# com.net
KiCad netlist of a schematic drawn in Altium Designer
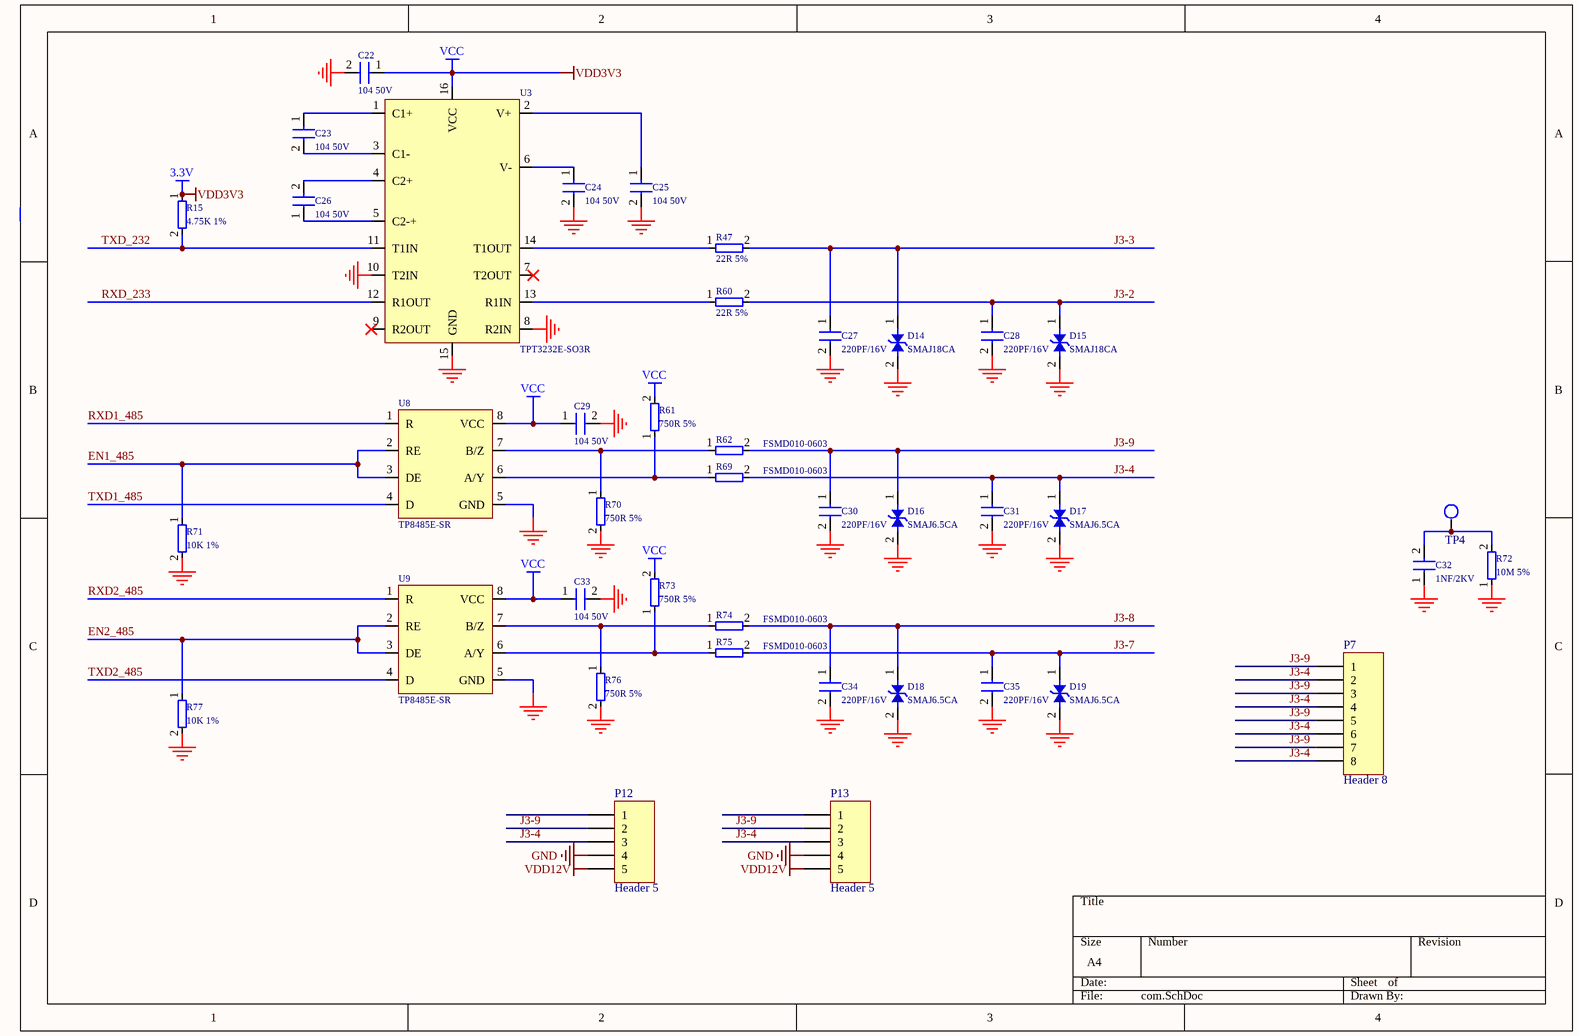
[diagram p0: com.SchDoc]

(export (version "E")
  (design (tool "Eeschema 10.0.6"))
  (components
    (comp (ref "C22") (value "104 50V") (footprint "0603C") (libsource (lib "*") (part "CAP")))
    (comp (ref "C23") (value "104 50V") (footprint "0603C") (libsource (lib "*") (part "CAP")))
    (comp (ref "C24") (value "104 50V") (footprint "0603C") (libsource (lib "*") (part "CAP")))
    (comp (ref "C25") (value "104 50V") (footprint "0603C") (libsource (lib "*") (part "CAP")))
    (comp (ref "C26") (value "104 50V") (footprint "0603C") (libsource (lib "*") (part "CAP")))
    (comp (ref "C27") (value "220PF/16V") (footprint "0603C") (libsource (lib "*") (part "CAP")))
    (comp (ref "C28") (value "220PF/16V") (footprint "0603C") (libsource (lib "*") (part "CAP")))
    (comp (ref "C29") (value "104 50V") (footprint "0603C") (libsource (lib "*") (part "CAP")))
    (comp (ref "C30") (value "220PF/16V") (footprint "0603C") (libsource (lib "*") (part "CAP")))
    (comp (ref "C31") (value "220PF/16V") (footprint "0603C") (libsource (lib "*") (part "CAP")))
    (comp (ref "C32") (value "1NF/2KV") (footprint "1206C") (libsource (lib "*") (part "CAP")))
    (comp (ref "C33") (value "104 50V") (footprint "0603C") (libsource (lib "*") (part "CAP")))
    (comp (ref "C34") (value "220PF/16V") (footprint "0603C") (libsource (lib "*") (part "CAP")))
    (comp (ref "C35") (value "220PF/16V") (footprint "0603C") (libsource (lib "*") (part "CAP")))
    (comp (ref "D14") (value "SMAJ18CA") (footprint "SMA") (libsource (lib "*") (part "D_ESD")))
    (comp (ref "D15") (value "SMAJ18CA") (footprint "SMA") (libsource (lib "*") (part "D_ESD")))
    (comp (ref "D16") (value "SMAJ6.5CA") (footprint "SMA") (libsource (lib "*") (part "D_ESD")))
    (comp (ref "D17") (value "SMAJ6.5CA") (footprint "SMA") (libsource (lib "*") (part "D_ESD")))
    (comp (ref "D18") (value "SMAJ6.5CA") (footprint "SMA") (libsource (lib "*") (part "D_ESD")))
    (comp (ref "D19") (value "SMAJ6.5CA") (footprint "SMA") (libsource (lib "*") (part "D_ESD")))
    (comp (ref "P7")
      (value "Header 8")
      (footprint "8X2.54MMZ")
      (description "Header, 8-Pin")
      (fields (field (name "PUBLISHER") "Altium Limited"))
      (libsource (lib "Miscellaneous Connectors") (part "Header 8"))
    )
    (comp (ref "P12")
      (value "Header 5")
      (footprint "5X2.54MMZ")
      (description "Header, 5-Pin")
      (fields (field (name "PUBLISHER") "Altium Limited"))
      (libsource (lib "Miscellaneous Connectors") (part "Header 5"))
    )
    (comp (ref "P13")
      (value "Header 5")
      (footprint "5X2.54MMZ")
      (description "Header, 5-Pin")
      (fields (field (name "PUBLISHER") "Altium Limited"))
      (libsource (lib "Miscellaneous Connectors") (part "Header 5"))
    )
    (comp (ref "R15") (value "4.75K 1%") (footprint "0603R") (libsource (lib "*") (part "RES")))
    (comp (ref "R47") (value "22R 5%") (footprint "0603R") (libsource (lib "*") (part "RES")))
    (comp (ref "R60") (value "22R 5%") (footprint "0603R") (libsource (lib "*") (part "RES")))
    (comp (ref "R61") (value "750R 5%") (footprint "0603R") (libsource (lib "*") (part "RES")))
    (comp (ref "R62") (value "FSMD010-0603") (footprint "0603R") (libsource (lib "*") (part "RES")))
    (comp (ref "R69") (value "FSMD010-0603") (footprint "0603R") (libsource (lib "*") (part "RES")))
    (comp (ref "R70") (value "750R 5%") (footprint "0603R") (libsource (lib "*") (part "RES")))
    (comp (ref "R71") (value "10K 1%") (footprint "0603R") (libsource (lib "*") (part "RES")))
    (comp (ref "R72") (value "10M 5%") (footprint "1206r") (libsource (lib "*") (part "RES")))
    (comp (ref "R73") (value "750R 5%") (footprint "0603R") (libsource (lib "*") (part "RES")))
    (comp (ref "R74") (value "FSMD010-0603") (footprint "0603R") (libsource (lib "*") (part "RES")))
    (comp (ref "R75") (value "FSMD010-0603") (footprint "0603R") (libsource (lib "*") (part "RES")))
    (comp (ref "R76") (value "750R 5%") (footprint "0603R") (libsource (lib "*") (part "RES")))
    (comp (ref "R77") (value "10K 1%") (footprint "0603R") (libsource (lib "*") (part "RES")))
    (comp (ref "TP4") (value "TPS") (footprint "tpd") (libsource (lib "stm32") (part "TPS")))
    (comp (ref "U3")
      (value "TPT3232E-SO3R")
      (footprint "SO-16Z")
      (libsource (lib "*") (part "TPT3232E-SO3R"))
    )
    (comp (ref "U8") (value "TP8485E-SR") (footprint "SO-8") (libsource (lib "*") (part "TP8485E-SR")))
    (comp (ref "U9") (value "TP8485E-SR") (footprint "SO-8") (libsource (lib "*") (part "TP8485E-SR")))
  )
  (nets
    (net (code "1") (name "/EN1_485") (class "Default")
      (node (ref "R71") (pin "1") (pinfunction "1_1") (pintype "passive"))
      (node (ref "U8") (pin "2") (pinfunction "RE_2") (pintype "passive"))
      (node (ref "U8") (pin "3") (pinfunction "DE_3") (pintype "passive"))
    )
    (net (code "2") (name "/EN2_485") (class "Default")
      (node (ref "R77") (pin "1") (pinfunction "1_1") (pintype "passive"))
      (node (ref "U9") (pin "2") (pinfunction "RE_2") (pintype "passive"))
      (node (ref "U9") (pin "3") (pinfunction "DE_3") (pintype "passive"))
    )
    (net (code "3") (name "/J3-2") (class "Default")
      (node (ref "C28") (pin "1") (pintype "passive"))
      (node (ref "D15") (pin "1") (pintype "passive"))
      (node (ref "R60") (pin "2") (pinfunction "2_2") (pintype "passive"))
    )
    (net (code "4") (name "/J3-3") (class "Default")
      (node (ref "C27") (pin "1") (pintype "passive"))
      (node (ref "D14") (pin "1") (pintype "passive"))
      (node (ref "R47") (pin "2") (pinfunction "2_2") (pintype "passive"))
    )
    (net (code "5") (name "/J3-4") (class "Default")
      (node (ref "C31") (pin "1") (pintype "passive"))
      (node (ref "D17") (pin "1") (pintype "passive"))
      (node (ref "P12") (pin "3") (pinfunction "3_3") (pintype "passive"))
      (node (ref "P13") (pin "3") (pinfunction "3_3") (pintype "passive"))
      (node (ref "P7") (pin "2") (pinfunction "2_2") (pintype "passive"))
      (node (ref "P7") (pin "4") (pinfunction "4_4") (pintype "passive"))
      (node (ref "P7") (pin "6") (pinfunction "6_6") (pintype "passive"))
      (node (ref "P7") (pin "8") (pinfunction "8_8") (pintype "passive"))
      (node (ref "R69") (pin "2") (pinfunction "2_2") (pintype "passive"))
    )
    (net (code "6") (name "/J3-7") (class "Default")
      (node (ref "C35") (pin "1") (pintype "passive"))
      (node (ref "D19") (pin "1") (pintype "passive"))
      (node (ref "R75") (pin "2") (pinfunction "2_2") (pintype "passive"))
    )
    (net (code "7") (name "/J3-8") (class "Default")
      (node (ref "C34") (pin "1") (pintype "passive"))
      (node (ref "D18") (pin "1") (pintype "passive"))
      (node (ref "R74") (pin "2") (pinfunction "2_2") (pintype "passive"))
    )
    (net (code "8") (name "/J3-9") (class "Default")
      (node (ref "C30") (pin "1") (pintype "passive"))
      (node (ref "D16") (pin "1") (pintype "passive"))
      (node (ref "P12") (pin "2") (pinfunction "2_2") (pintype "passive"))
      (node (ref "P13") (pin "2") (pinfunction "2_2") (pintype "passive"))
      (node (ref "P7") (pin "1") (pinfunction "1_1") (pintype "passive"))
      (node (ref "P7") (pin "3") (pinfunction "3_3") (pintype "passive"))
      (node (ref "P7") (pin "5") (pinfunction "5_5") (pintype "passive"))
      (node (ref "P7") (pin "7") (pinfunction "7_7") (pintype "passive"))
      (node (ref "R62") (pin "2") (pinfunction "2_2") (pintype "passive"))
    )
    (net (code "9") (name "/RXD1_485") (class "Default")
      (node (ref "U8") (pin "1") (pinfunction "R_1") (pintype "passive"))
    )
    (net (code "10") (name "/RXD2_485") (class "Default")
      (node (ref "U9") (pin "1") (pinfunction "R_1") (pintype "passive"))
    )
    (net (code "11") (name "/RXD_233") (class "Default")
      (node (ref "U3") (pin "12") (pinfunction "R1OUT_12") (pintype "passive"))
    )
    (net (code "12") (name "/TXD1_485") (class "Default")
      (node (ref "U8") (pin "4") (pinfunction "D_4") (pintype "passive"))
    )
    (net (code "13") (name "/TXD2_485") (class "Default")
      (node (ref "U9") (pin "4") (pinfunction "D_4") (pintype "passive"))
    )
    (net (code "14") (name "/TXD_232") (class "Default")
      (node (ref "R15") (pin "2") (pinfunction "2_2") (pintype "passive"))
      (node (ref "U3") (pin "11") (pinfunction "T1IN_11") (pintype "passive"))
    )
    (net (code "15") (name "3.3V") (class "Default")
      (node (ref "C22") (pin "1") (pintype "passive"))
      (node (ref "C29") (pin "1") (pintype "passive"))
      (node (ref "C33") (pin "1") (pintype "passive"))
      (node (ref "R15") (pin "1") (pinfunction "1_1") (pintype "passive"))
      (node (ref "R61") (pin "2") (pinfunction "2_2") (pintype "passive"))
      (node (ref "R73") (pin "2") (pinfunction "2_2") (pintype "passive"))
      (node (ref "U3") (pin "16") (pinfunction "VCC_16") (pintype "passive"))
      (node (ref "U8") (pin "8") (pinfunction "VCC_8") (pintype "passive"))
      (node (ref "U9") (pin "8") (pinfunction "VCC_8") (pintype "passive"))
    )
    (net (code "16") (name "GND") (class "Default")
      (node (ref "C22") (pin "2") (pintype "passive"))
      (node (ref "C24") (pin "2") (pintype "passive"))
      (node (ref "C25") (pin "2") (pintype "passive"))
      (node (ref "C27") (pin "2") (pintype "passive"))
      (node (ref "C28") (pin "2") (pintype "passive"))
      (node (ref "C29") (pin "2") (pintype "passive"))
      (node (ref "C30") (pin "2") (pintype "passive"))
      (node (ref "C31") (pin "2") (pintype "passive"))
      (node (ref "C32") (pin "1") (pintype "passive"))
      (node (ref "C33") (pin "2") (pintype "passive"))
      (node (ref "C34") (pin "2") (pintype "passive"))
      (node (ref "C35") (pin "2") (pintype "passive"))
      (node (ref "D14") (pin "2") (pintype "passive"))
      (node (ref "D15") (pin "2") (pintype "passive"))
      (node (ref "D16") (pin "2") (pintype "passive"))
      (node (ref "D17") (pin "2") (pintype "passive"))
      (node (ref "D18") (pin "2") (pintype "passive"))
      (node (ref "D19") (pin "2") (pintype "passive"))
      (node (ref "P12") (pin "4") (pinfunction "4_4") (pintype "passive"))
      (node (ref "P13") (pin "4") (pinfunction "4_4") (pintype "passive"))
      (node (ref "R70") (pin "2") (pinfunction "2_2") (pintype "passive"))
      (node (ref "R71") (pin "2") (pinfunction "2_2") (pintype "passive"))
      (node (ref "R72") (pin "1") (pinfunction "1_1") (pintype "passive"))
      (node (ref "R76") (pin "2") (pinfunction "2_2") (pintype "passive"))
      (node (ref "R77") (pin "2") (pinfunction "2_2") (pintype "passive"))
      (node (ref "U3") (pin "10") (pinfunction "T2IN_10") (pintype "passive"))
      (node (ref "U3") (pin "15") (pinfunction "GND_15") (pintype "passive"))
      (node (ref "U3") (pin "8") (pinfunction "R2IN_8") (pintype "passive"))
      (node (ref "U8") (pin "5") (pinfunction "GND_5") (pintype "passive"))
      (node (ref "U9") (pin "5") (pinfunction "GND_5") (pintype "passive"))
    )
    (net (code "17") (name "Net-(C32-Pad2)") (class "Default")
      (node (ref "C32") (pin "2") (pintype "passive"))
      (node (ref "R72") (pin "2") (pinfunction "2_2") (pintype "passive"))
      (node (ref "TP4") (pin "1") (pinfunction "1_1") (pintype "passive"))
    )
    (net (code "18") (name "Net-(U3-C1+)") (class "Default")
      (node (ref "C23") (pin "1") (pintype "passive"))
      (node (ref "U3") (pin "1") (pinfunction "C1+_1") (pintype "passive"))
    )
    (net (code "19") (name "Net-(U3-C1-)") (class "Default")
      (node (ref "C23") (pin "2") (pintype "passive"))
      (node (ref "U3") (pin "3") (pinfunction "C1-_3") (pintype "passive"))
    )
    (net (code "20") (name "Net-(U3-C2+)") (class "Default")
      (node (ref "C26") (pin "2") (pintype "passive"))
      (node (ref "U3") (pin "4") (pinfunction "C2+_4") (pintype "passive"))
    )
    (net (code "21") (name "Net-(U3-C2-+)") (class "Default")
      (node (ref "C26") (pin "1") (pintype "passive"))
      (node (ref "U3") (pin "5") (pinfunction "C2-+_5") (pintype "passive"))
    )
    (net (code "22") (name "Net-(U3-R1IN)") (class "Default")
      (node (ref "R60") (pin "1") (pinfunction "1_1") (pintype "passive"))
      (node (ref "U3") (pin "13") (pinfunction "R1IN_13") (pintype "passive"))
    )
    (net (code "23") (name "Net-(U3-T1OUT)") (class "Default")
      (node (ref "R47") (pin "1") (pinfunction "1_1") (pintype "passive"))
      (node (ref "U3") (pin "14") (pinfunction "T1OUT_14") (pintype "passive"))
    )
    (net (code "24") (name "Net-(U3-V+)") (class "Default")
      (node (ref "C25") (pin "1") (pintype "passive"))
      (node (ref "U3") (pin "2") (pinfunction "V+_2") (pintype "passive"))
    )
    (net (code "25") (name "Net-(U3-V-)") (class "Default")
      (node (ref "C24") (pin "1") (pintype "passive"))
      (node (ref "U3") (pin "6") (pinfunction "V-_6") (pintype "passive"))
    )
    (net (code "26") (name "Net-(U8-A{slash}Y)") (class "Default")
      (node (ref "R61") (pin "1") (pinfunction "1_1") (pintype "passive"))
      (node (ref "R69") (pin "1") (pinfunction "1_1") (pintype "passive"))
      (node (ref "U8") (pin "6") (pinfunction "A/Y_6") (pintype "passive"))
    )
    (net (code "27") (name "Net-(U8-B{slash}Z)") (class "Default")
      (node (ref "R62") (pin "1") (pinfunction "1_1") (pintype "passive"))
      (node (ref "R70") (pin "1") (pinfunction "1_1") (pintype "passive"))
      (node (ref "U8") (pin "7") (pinfunction "B/Z_7") (pintype "passive"))
    )
    (net (code "28") (name "Net-(U9-A{slash}Y)") (class "Default")
      (node (ref "R73") (pin "1") (pinfunction "1_1") (pintype "passive"))
      (node (ref "R75") (pin "1") (pinfunction "1_1") (pintype "passive"))
      (node (ref "U9") (pin "6") (pinfunction "A/Y_6") (pintype "passive"))
    )
    (net (code "29") (name "Net-(U9-B{slash}Z)") (class "Default")
      (node (ref "R74") (pin "1") (pinfunction "1_1") (pintype "passive"))
      (node (ref "R76") (pin "1") (pinfunction "1_1") (pintype "passive"))
      (node (ref "U9") (pin "7") (pinfunction "B/Z_7") (pintype "passive"))
    )
    (net (code "30") (name "VDD12V") (class "Default")
      (node (ref "P12") (pin "5") (pinfunction "5_5") (pintype "passive"))
      (node (ref "P13") (pin "5") (pinfunction "5_5") (pintype "passive"))
    )
    (net (code "31") (name "unconnected-(P12-Pad1)") (class "Default")
      (node (ref "P12") (pin "1") (pinfunction "1_1") (pintype "passive"))
    )
    (net (code "32") (name "unconnected-(P13-Pad1)") (class "Default")
      (node (ref "P13") (pin "1") (pinfunction "1_1") (pintype "passive"))
    )
    (net (code "33") (name "unconnected-(U3-R2OUT-Pad9)") (class "Default")
      (node (ref "U3") (pin "9") (pinfunction "R2OUT_9") (pintype "passive+no_connect"))
    )
    (net (code "34") (name "unconnected-(U3-T2OUT-Pad7)") (class "Default")
      (node (ref "U3") (pin "7") (pinfunction "T2OUT_7") (pintype "passive+no_connect"))
    )
  )
)
